# develer_2L_A4.net
KiCad netlist of a schematic drawn in Altium Designer
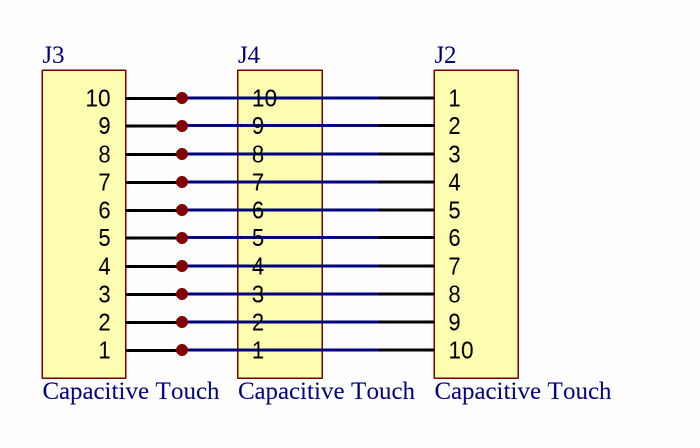
[diagram p0: develer_2L_A4.SchDoc]

(export (version "E")
  (design (tool "Eeschema 10.0.6"))
  (components
    (comp (ref "J2")
      (value "Capacitive Touch")
      (footprint "fcc-zif_10pin_0.5mm")
      (description "10-pin, 0.5mm, SMT, ZIF, Horizontal, Top Contact")
      (fields (field (name "PUBLISHER") "Altium Limited"))
      (libsource (lib "") (part "Header 10_1"))
    )
    (comp (ref "J3")
      (value "Capacitive Touch")
      (footprint "fcc-zif_10pin_0.5mm")
      (description "10-pin, 0.5mm, SMT, ZIF, Horizontal, Top Contact")
      (fields (field (name "PUBLISHER") "Altium Limited"))
      (libsource (lib "Miscellaneous Connectors") (part "Header 10"))
    )
    (comp (ref "J4")
      (value "Capacitive Touch")
      (footprint "fcc-zif_10pin_0.5mm")
      (description "10-pin, 0.5mm, SMT, ZIF, Horizontal, Top Contact")
      (fields (field (name "PUBLISHER") "Altium Limited"))
      (libsource (lib "") (part "Header 10_2"))
    )
  )
  (nets
    (net (code "1") (name "Net-(J2-Pad1)") (class "Default")
      (node (ref "J2") (pin "1") (pinfunction "1_1") (pintype "passive"))
      (node (ref "J3") (pin "10") (pinfunction "10_10") (pintype "passive"))
      (node (ref "J4") (pin "10") (pinfunction "10_10") (pintype "passive"))
    )
    (net (code "2") (name "Net-(J2-Pad2)") (class "Default")
      (node (ref "J2") (pin "2") (pinfunction "2_2") (pintype "passive"))
      (node (ref "J3") (pin "9") (pinfunction "9_9") (pintype "passive"))
      (node (ref "J4") (pin "9") (pinfunction "9_9") (pintype "passive"))
    )
    (net (code "3") (name "Net-(J2-Pad3)") (class "Default")
      (node (ref "J2") (pin "3") (pinfunction "3_3") (pintype "passive"))
      (node (ref "J3") (pin "8") (pinfunction "8_8") (pintype "passive"))
      (node (ref "J4") (pin "8") (pinfunction "8_8") (pintype "passive"))
    )
    (net (code "4") (name "Net-(J2-Pad4)") (class "Default")
      (node (ref "J2") (pin "4") (pinfunction "4_4") (pintype "passive"))
      (node (ref "J3") (pin "7") (pinfunction "7_7") (pintype "passive"))
      (node (ref "J4") (pin "7") (pinfunction "7_7") (pintype "passive"))
    )
    (net (code "5") (name "Net-(J2-Pad5)") (class "Default")
      (node (ref "J2") (pin "5") (pinfunction "5_5") (pintype "passive"))
      (node (ref "J3") (pin "6") (pinfunction "6_6") (pintype "passive"))
      (node (ref "J4") (pin "6") (pinfunction "6_6") (pintype "passive"))
    )
    (net (code "6") (name "Net-(J2-Pad6)") (class "Default")
      (node (ref "J2") (pin "6") (pinfunction "6_6") (pintype "passive"))
      (node (ref "J3") (pin "5") (pinfunction "5_5") (pintype "passive"))
      (node (ref "J4") (pin "5") (pinfunction "5_5") (pintype "passive"))
    )
    (net (code "7") (name "Net-(J2-Pad7)") (class "Default")
      (node (ref "J2") (pin "7") (pinfunction "7_7") (pintype "passive"))
      (node (ref "J3") (pin "4") (pinfunction "4_4") (pintype "passive"))
      (node (ref "J4") (pin "4") (pinfunction "4_4") (pintype "passive"))
    )
    (net (code "8") (name "Net-(J2-Pad8)") (class "Default")
      (node (ref "J2") (pin "8") (pinfunction "8_8") (pintype "passive"))
      (node (ref "J3") (pin "3") (pinfunction "3_3") (pintype "passive"))
      (node (ref "J4") (pin "3") (pinfunction "3_3") (pintype "passive"))
    )
    (net (code "9") (name "Net-(J2-Pad9)") (class "Default")
      (node (ref "J2") (pin "9") (pinfunction "9_9") (pintype "passive"))
      (node (ref "J3") (pin "2") (pinfunction "2_2") (pintype "passive"))
      (node (ref "J4") (pin "2") (pinfunction "2_2") (pintype "passive"))
    )
    (net (code "10") (name "Net-(J2-Pad10)") (class "Default")
      (node (ref "J2") (pin "10") (pinfunction "10_10") (pintype "passive"))
      (node (ref "J3") (pin "1") (pinfunction "1_1") (pintype "passive"))
      (node (ref "J4") (pin "1") (pinfunction "1_1") (pintype "passive"))
    )
  )
)
